# 40_Flash-eMMC_Flash.net
KiCad netlist of a schematic drawn in Altium Designer
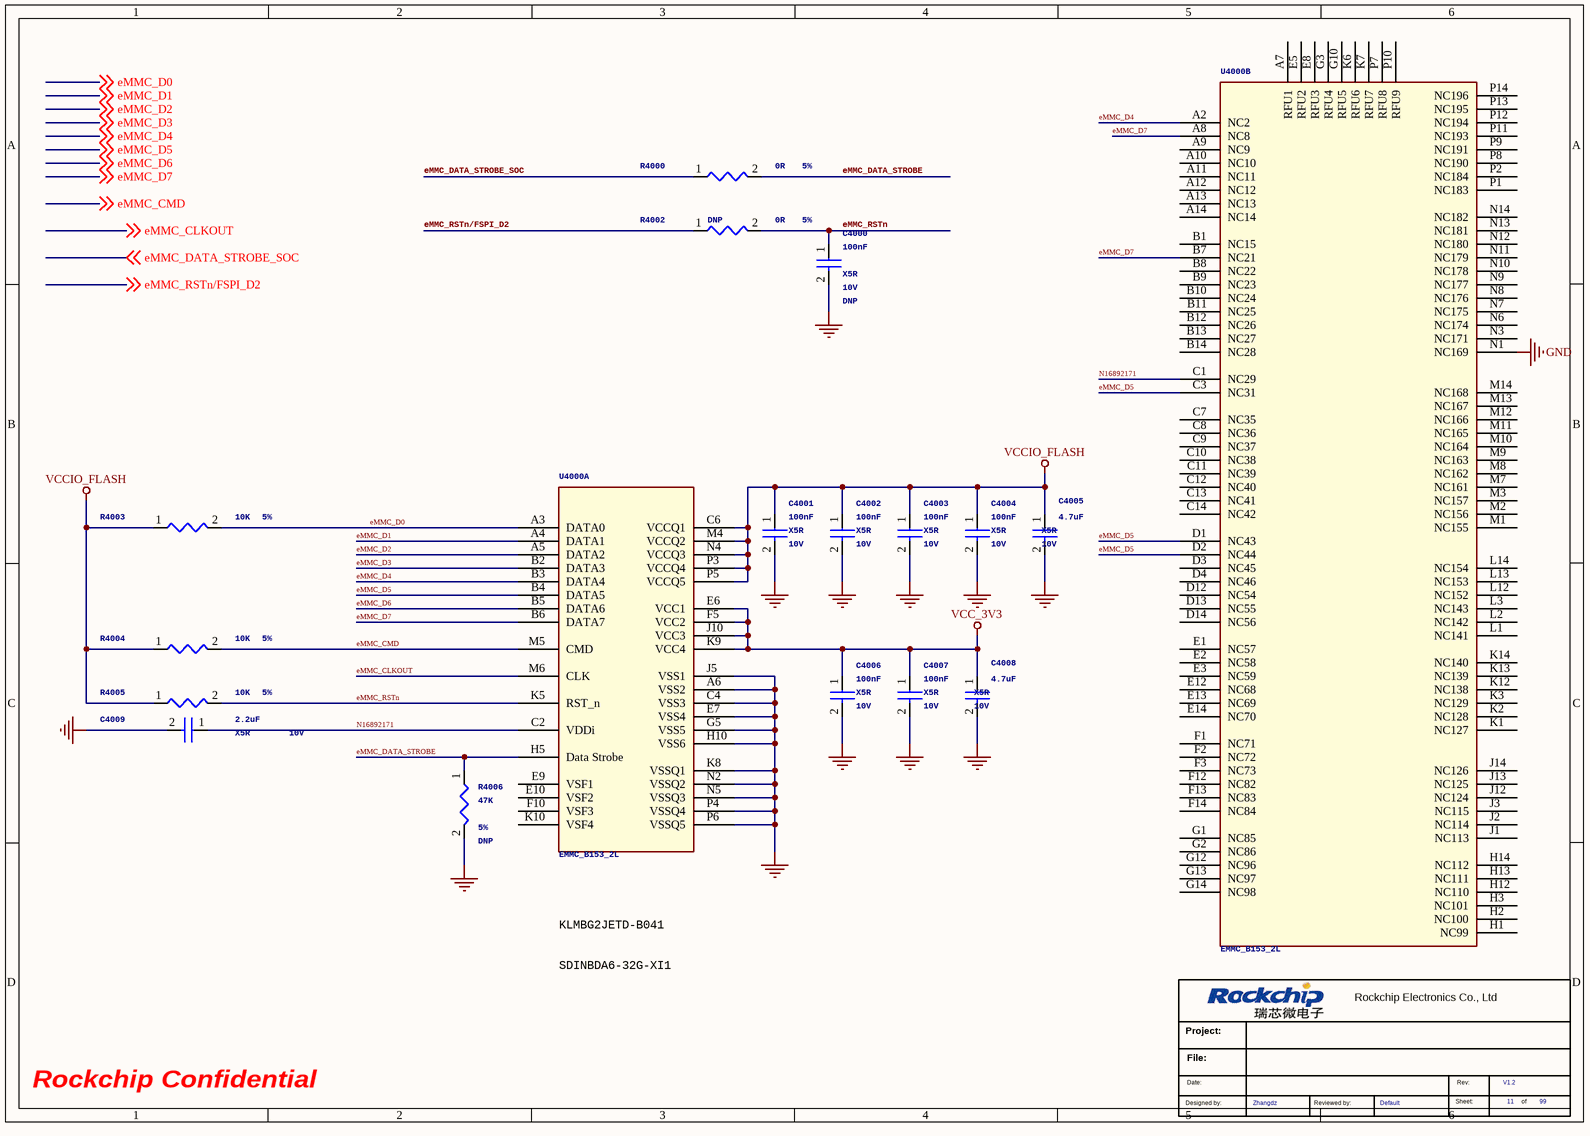
[diagram p0: 40.Flash-eMMC Flash.SchDoc]

(export (version "E")
  (design (tool "Eeschema 10.0.6"))
  (components
    (comp (ref "*")
      (value "Rockchip_new")
      (fields
        (field (name "SCHEMATIC PAGE COUNT") "99")
        (field (name "SCHEMATIC PAGE NUMBER") "11")
        (field (name "DESIGNER") "Zhangdz")
        (field (name "REVISION") "V1.2")
        (field (name "CHECK") "Default")
      )
      (libsource (lib "*") (part "Rockchip_new"))
    )
    (comp (ref "C4000")
      (value "100nF")
      (footprint "C0402")
      (description "cap,100.00nF,+/-10%,10V,X5R,C0402")
      (fields
        (field (name "VOLTAGE") "10V")
        (field (name "DIELECTRIC") "X5R")
        (field (name "OPTION") "DNP")
        (field (name "TOLERANCE") "10%")
        (field (name "MANUFACTURER") "TDK")
        (field (name "CREATED BY") "JJJ")
      )
      (libsource (lib "*") (part "CAP NP"))
    )
    (comp (ref "C4001")
      (value "100nF")
      (footprint "C0402")
      (description "cap,100.00nF,+/-10%,10V,X5R,C0402")
      (fields
        (field (name "VOLTAGE") "10V")
        (field (name "DIELECTRIC") "X5R")
        (field (name "MANUFACTURER") "TDK")
        (field (name "TOLERANCE") "10%")
        (field (name "CREATED BY") "JJJ")
      )
      (libsource (lib "*") (part "CAP NP"))
    )
    (comp (ref "C4002")
      (value "100nF")
      (footprint "C0402")
      (description "cap,100.00nF,+/-10%,10V,X5R,C0402")
      (fields
        (field (name "VOLTAGE") "10V")
        (field (name "DIELECTRIC") "X5R")
        (field (name "TOLERANCE") "10%")
        (field (name "MANUFACTURER") "TDK")
        (field (name "CREATED BY") "JJJ")
      )
      (libsource (lib "*") (part "CAP NP"))
    )
    (comp (ref "C4003")
      (value "100nF")
      (footprint "C0402")
      (description "cap,100.00nF,+/-10%,10V,X5R,C0402")
      (fields
        (field (name "VOLTAGE") "10V")
        (field (name "DIELECTRIC") "X5R")
        (field (name "TOLERANCE") "10%")
        (field (name "MANUFACTURER") "TDK")
        (field (name "CREATED BY") "JJJ")
      )
      (libsource (lib "*") (part "CAP NP"))
    )
    (comp (ref "C4004")
      (value "100nF")
      (footprint "C0402")
      (description "cap,100.00nF,+/-10%,10V,X5R,C0402")
      (fields
        (field (name "VOLTAGE") "10V")
        (field (name "DIELECTRIC") "X5R")
        (field (name "MANUFACTURER") "TDK")
        (field (name "TOLERANCE") "10%")
        (field (name "CREATED BY") "JJJ")
      )
      (libsource (lib "*") (part "CAP NP"))
    )
    (comp (ref "C4005")
      (value "4.7uF")
      (footprint "C0603")
      (description "cap,4.70uF,+/-10%,10V,X5R,C0603")
      (fields
        (field (name "VOLTAGE") "10V")
        (field (name "DIELECTRIC") "X5R")
        (field (name "MANUFACTURER") "TDK")
        (field (name "TOLERANCE") "10%")
        (field (name "CREATED BY") "JJJ")
      )
      (libsource (lib "*") (part "CAP NP"))
    )
    (comp (ref "C4006")
      (value "100nF")
      (footprint "C0402")
      (description "cap,100.00nF,+/-10%,10V,X5R,C0402")
      (fields
        (field (name "VOLTAGE") "10V")
        (field (name "DIELECTRIC") "X5R")
        (field (name "TOLERANCE") "10%")
        (field (name "MANUFACTURER") "TDK")
        (field (name "CREATED BY") "JJJ")
      )
      (libsource (lib "*") (part "CAP NP"))
    )
    (comp (ref "C4007")
      (value "100nF")
      (footprint "C0402")
      (description "cap,100.00nF,+/-10%,10V,X5R,C0402")
      (fields
        (field (name "VOLTAGE") "10V")
        (field (name "DIELECTRIC") "X5R")
        (field (name "TOLERANCE") "10%")
        (field (name "MANUFACTURER") "TDK")
        (field (name "CREATED BY") "JJJ")
      )
      (libsource (lib "*") (part "CAP NP"))
    )
    (comp (ref "C4008")
      (value "4.7uF")
      (footprint "C0603")
      (description "cap,4.70uF,+/-10%,10V,X5R,C0603")
      (fields
        (field (name "VOLTAGE") "10V")
        (field (name "DIELECTRIC") "X5R")
        (field (name "MANUFACTURER") "TDK")
        (field (name "TOLERANCE") "10%")
        (field (name "CREATED BY") "JJJ")
      )
      (libsource (lib "*") (part "CAP NP"))
    )
    (comp (ref "C4009")
      (value "2.2uF")
      (footprint "C0402")
      (description "cap,2.20uF,+/-10%,10V,X5R,C0402")
      (fields
        (field (name "VOLTAGE") "10V")
        (field (name "DIELECTRIC") "X5R")
        (field (name "TOLERANCE") "10%")
        (field (name "MANUFACTURER") "TDK")
        (field (name "CREATED BY") "JJJ")
      )
      (libsource (lib "*") (part "CAP NP"))
    )
    (comp (ref "R4000")
      (value "0R")
      (footprint "R0402")
      (description "通用厚膜电阻,0R,+/-5%,R0402,1/16W.")
      (fields
        (field (name "TOLERANCE") "5%")
        (field (name "MANUFACTURER") "YAGEO")
        (field (name "CREATED BY") "YTL")
      )
      (libsource (lib "*") (part "RESISTOR"))
    )
    (comp (ref "R4002")
      (value "0R")
      (footprint "R0402")
      (description "通用厚膜电阻,0R,+/-5%,R0402,1/16W.")
      (fields
        (field (name "TOLERANCE") "5%")
        (field (name "MANUFACTURER") "YAGEO")
        (field (name "OPTION") "DNP")
        (field (name "CREATED BY") "YTL")
      )
      (libsource (lib "*") (part "RESISTOR"))
    )
    (comp (ref "R4003")
      (value "10K")
      (footprint "R0402")
      (description "通用厚膜电阻,10K,+/-5%,R0402,1/16W.")
      (fields
        (field (name "TOLERANCE") "5%")
        (field (name "MANUFACTURER") "YAGEO")
        (field (name "CREATED BY") "YTL")
      )
      (libsource (lib "*") (part "RESISTOR"))
    )
    (comp (ref "R4004")
      (value "10K")
      (footprint "R0402")
      (description "通用厚膜电阻,10K,+/-5%,R0402,1/16W.")
      (fields
        (field (name "TOLERANCE") "5%")
        (field (name "MANUFACTURER") "YAGEO")
        (field (name "CREATED BY") "YTL")
      )
      (libsource (lib "*") (part "RESISTOR"))
    )
    (comp (ref "R4005")
      (value "10K")
      (footprint "R0402")
      (description "通用厚膜电阻,10K,+/-5%,R0402,1/16W.")
      (fields
        (field (name "TOLERANCE") "5%")
        (field (name "MANUFACTURER") "YAGEO")
        (field (name "CREATED BY") "YTL")
      )
      (libsource (lib "*") (part "RESISTOR"))
    )
    (comp (ref "R4006")
      (value "47K")
      (footprint "R0402")
      (description "通用厚膜电阻,47K,+/-5%,R0402,1/16W.")
      (fields
        (field (name "TOLERANCE") "5%")
        (field (name "OPTION") "DNP")
        (field (name "MANUFACTURER") "YAGEO")
        (field (name "CREATED BY") "YTL")
      )
      (libsource (lib "*") (part "RESISTOR"))
    )
    (comp (ref "U4000")
      (value "EMMC_B153_2L")
      (footprint "BGA153_13RX11R5X0R9_2L")
      (description "EMMC_B153_2L,更好的满足工艺需求，Fanout方式部分走线跨接再球位上，挖除A1\\C5球位")
      (fields (field (name "CREATED BY") "YWQ"))
      (libsource (lib "*") (part "INAND_EMMC_153_2L"))
    )
  )
  (nets
    (net (code "1") (name "/N16892171") (class "Default")
      (node (ref "C4009") (pin "1") (pinfunction "1_1") (pintype "passive"))
      (node (ref "U4000") (pin "C1") (pinfunction "NC29_C1") (pintype "passive"))
      (node (ref "U4000") (pin "C2") (pinfunction "VDDi_C2") (pintype "passive"))
    )
    (net (code "2") (name "/eMMC_DATA_STROBE") (class "Default")
      (node (ref "R4000") (pin "2") (pinfunction "2_2") (pintype "passive"))
      (node (ref "R4006") (pin "1") (pinfunction "1_1") (pintype "passive"))
      (node (ref "U4000") (pin "H5") (pinfunction "Data_Strobe_H5") (pintype "passive"))
    )
    (net (code "3") (name "/eMMC_RSTn") (class "Default")
      (node (ref "C4000") (pin "1") (pinfunction "1_1") (pintype "passive"))
      (node (ref "R4002") (pin "2") (pinfunction "2_2") (pintype "passive"))
      (node (ref "R4005") (pin "2") (pinfunction "2_2") (pintype "passive"))
      (node (ref "U4000") (pin "K5") (pinfunction "RST_n_K5") (pintype "passive"))
    )
    (net (code "4") (name "GND") (class "Default")
      (node (ref "C4000") (pin "2") (pinfunction "2_2") (pintype "passive"))
      (node (ref "C4001") (pin "2") (pinfunction "2_2") (pintype "passive"))
      (node (ref "C4002") (pin "2") (pinfunction "2_2") (pintype "passive"))
      (node (ref "C4003") (pin "2") (pinfunction "2_2") (pintype "passive"))
      (node (ref "C4004") (pin "2") (pinfunction "2_2") (pintype "passive"))
      (node (ref "C4005") (pin "2") (pinfunction "2_2") (pintype "passive"))
      (node (ref "C4006") (pin "2") (pinfunction "2_2") (pintype "passive"))
      (node (ref "C4007") (pin "2") (pinfunction "2_2") (pintype "passive"))
      (node (ref "C4008") (pin "2") (pinfunction "2_2") (pintype "passive"))
      (node (ref "C4009") (pin "2") (pinfunction "2_2") (pintype "passive"))
      (node (ref "R4006") (pin "2") (pinfunction "2_2") (pintype "passive"))
      (node (ref "U4000") (pin "A6") (pinfunction "VSS2_A6") (pintype "passive"))
      (node (ref "U4000") (pin "C4") (pinfunction "VSS3_C4") (pintype "passive"))
      (node (ref "U4000") (pin "E7") (pinfunction "VSS4_E7") (pintype "passive"))
      (node (ref "U4000") (pin "G5") (pinfunction "VSS5_G5") (pintype "passive"))
      (node (ref "U4000") (pin "H10") (pinfunction "VSS6_H10") (pintype "passive"))
      (node (ref "U4000") (pin "J5") (pinfunction "VSS1_J5") (pintype "passive"))
      (node (ref "U4000") (pin "K8") (pinfunction "VSSQ1_K8") (pintype "passive"))
      (node (ref "U4000") (pin "N1") (pinfunction "NC169_N1") (pintype "passive"))
      (node (ref "U4000") (pin "N2") (pinfunction "VSSQ2_N2") (pintype "passive"))
      (node (ref "U4000") (pin "N5") (pinfunction "VSSQ3_N5") (pintype "passive"))
      (node (ref "U4000") (pin "P4") (pinfunction "VSSQ4_P4") (pintype "passive"))
      (node (ref "U4000") (pin "P6") (pinfunction "VSSQ5_P6") (pintype "passive"))
    )
    (net (code "5") (name "VCCIO_FLASH") (class "Default")
      (node (ref "C4001") (pin "1") (pinfunction "1_1") (pintype "passive"))
      (node (ref "C4002") (pin "1") (pinfunction "1_1") (pintype "passive"))
      (node (ref "C4003") (pin "1") (pinfunction "1_1") (pintype "passive"))
      (node (ref "C4004") (pin "1") (pinfunction "1_1") (pintype "passive"))
      (node (ref "C4005") (pin "1") (pinfunction "1_1") (pintype "passive"))
      (node (ref "R4003") (pin "1") (pinfunction "1_1") (pintype "passive"))
      (node (ref "R4004") (pin "1") (pinfunction "1_1") (pintype "passive"))
      (node (ref "R4005") (pin "1") (pinfunction "1_1") (pintype "passive"))
      (node (ref "U4000") (pin "C6") (pinfunction "VCCQ1_C6") (pintype "passive"))
      (node (ref "U4000") (pin "M4") (pinfunction "VCCQ2_M4") (pintype "passive"))
      (node (ref "U4000") (pin "N4") (pinfunction "VCCQ3_N4") (pintype "passive"))
      (node (ref "U4000") (pin "P3") (pinfunction "VCCQ4_P3") (pintype "passive"))
      (node (ref "U4000") (pin "P5") (pinfunction "VCCQ5_P5") (pintype "passive"))
    )
    (net (code "6") (name "VCC_3V3") (class "Default")
      (node (ref "C4006") (pin "1") (pinfunction "1_1") (pintype "passive"))
      (node (ref "C4007") (pin "1") (pinfunction "1_1") (pintype "passive"))
      (node (ref "C4008") (pin "1") (pinfunction "1_1") (pintype "passive"))
      (node (ref "U4000") (pin "E6") (pinfunction "VCC1_E6") (pintype "passive"))
      (node (ref "U4000") (pin "F5") (pinfunction "VCC2_F5") (pintype "passive"))
      (node (ref "U4000") (pin "J10") (pinfunction "VCC3_J10") (pintype "passive"))
      (node (ref "U4000") (pin "K9") (pinfunction "VCC4_K9") (pintype "passive"))
    )
    (net (code "7") (name "eMMC_CLKOUT") (class "Default")
      (node (ref "U4000") (pin "M6") (pinfunction "CLK_M6") (pintype "passive"))
    )
    (net (code "8") (name "eMMC_CMD") (class "Default")
      (node (ref "R4004") (pin "2") (pinfunction "2_2") (pintype "passive"))
      (node (ref "U4000") (pin "M5") (pinfunction "CMD_M5") (pintype "passive"))
    )
    (net (code "9") (name "eMMC_D0") (class "Default")
      (node (ref "R4003") (pin "2") (pinfunction "2_2") (pintype "passive"))
      (node (ref "U4000") (pin "A3") (pinfunction "DATA0_A3") (pintype "passive"))
    )
    (net (code "10") (name "eMMC_D1") (class "Default")
      (node (ref "U4000") (pin "A4") (pinfunction "DATA1_A4") (pintype "passive"))
    )
    (net (code "11") (name "eMMC_D2") (class "Default")
      (node (ref "U4000") (pin "A5") (pinfunction "DATA2_A5") (pintype "passive"))
    )
    (net (code "12") (name "eMMC_D3") (class "Default")
      (node (ref "U4000") (pin "B2") (pinfunction "DATA3_B2") (pintype "passive"))
    )
    (net (code "13") (name "eMMC_D4") (class "Default")
      (node (ref "U4000") (pin "A2") (pinfunction "NC2_A2") (pintype "passive"))
      (node (ref "U4000") (pin "B3") (pinfunction "DATA4_B3") (pintype "passive"))
    )
    (net (code "14") (name "eMMC_D5") (class "Default")
      (node (ref "U4000") (pin "B4") (pinfunction "DATA5_B4") (pintype "passive"))
      (node (ref "U4000") (pin "C3") (pinfunction "NC31_C3") (pintype "passive"))
      (node (ref "U4000") (pin "D1") (pinfunction "NC43_D1") (pintype "passive"))
      (node (ref "U4000") (pin "D2") (pinfunction "NC44_D2") (pintype "passive"))
    )
    (net (code "15") (name "eMMC_D6") (class "Default")
      (node (ref "U4000") (pin "B5") (pinfunction "DATA6_B5") (pintype "passive"))
    )
    (net (code "16") (name "eMMC_D7") (class "Default")
      (node (ref "U4000") (pin "A8") (pinfunction "NC8_A8") (pintype "passive"))
      (node (ref "U4000") (pin "B6") (pinfunction "DATA7_B6") (pintype "passive"))
      (node (ref "U4000") (pin "B7") (pinfunction "NC21_B7") (pintype "passive"))
    )
    (net (code "17") (name "eMMC_DATA_STROBE_SOC") (class "Default")
      (node (ref "R4000") (pin "1") (pinfunction "1_1") (pintype "passive"))
    )
    (net (code "18") (name "eMMC_RSTn{slash}FSPI_D2") (class "Default")
      (node (ref "R4002") (pin "1") (pinfunction "1_1") (pintype "passive"))
    )
    (net (code "19") (name "unconnected-(U4000A-VSF1-PadE9)") (class "Default")
      (node (ref "U4000") (pin "E9") (pinfunction "VSF1_E9") (pintype "passive"))
    )
    (net (code "20") (name "unconnected-(U4000A-VSF2-PadE10)") (class "Default")
      (node (ref "U4000") (pin "E10") (pinfunction "VSF2_E10") (pintype "passive"))
    )
    (net (code "21") (name "unconnected-(U4000A-VSF3-PadF10)") (class "Default")
      (node (ref "U4000") (pin "F10") (pinfunction "VSF3_F10") (pintype "passive"))
    )
    (net (code "22") (name "unconnected-(U4000A-VSF4-PadK10)") (class "Default")
      (node (ref "U4000") (pin "K10") (pinfunction "VSF4_K10") (pintype "passive"))
    )
    (net (code "23") (name "unconnected-(U4000B-NC9-PadA9)") (class "Default")
      (node (ref "U4000") (pin "A9") (pinfunction "NC9_A9") (pintype "passive"))
    )
    (net (code "24") (name "unconnected-(U4000B-NC10-PadA10)") (class "Default")
      (node (ref "U4000") (pin "A10") (pinfunction "NC10_A10") (pintype "passive"))
    )
    (net (code "25") (name "unconnected-(U4000B-NC11-PadA11)") (class "Default")
      (node (ref "U4000") (pin "A11") (pinfunction "NC11_A11") (pintype "passive"))
    )
    (net (code "26") (name "unconnected-(U4000B-NC12-PadA12)") (class "Default")
      (node (ref "U4000") (pin "A12") (pinfunction "NC12_A12") (pintype "passive"))
    )
    (net (code "27") (name "unconnected-(U4000B-NC13-PadA13)") (class "Default")
      (node (ref "U4000") (pin "A13") (pinfunction "NC13_A13") (pintype "passive"))
    )
    (net (code "28") (name "unconnected-(U4000B-NC14-PadA14)") (class "Default")
      (node (ref "U4000") (pin "A14") (pinfunction "NC14_A14") (pintype "passive"))
    )
    (net (code "29") (name "unconnected-(U4000B-NC15-PadB1)") (class "Default")
      (node (ref "U4000") (pin "B1") (pinfunction "NC15_B1") (pintype "passive"))
    )
    (net (code "30") (name "unconnected-(U4000B-NC22-PadB8)") (class "Default")
      (node (ref "U4000") (pin "B8") (pinfunction "NC22_B8") (pintype "passive"))
    )
    (net (code "31") (name "unconnected-(U4000B-NC23-PadB9)") (class "Default")
      (node (ref "U4000") (pin "B9") (pinfunction "NC23_B9") (pintype "passive"))
    )
    (net (code "32") (name "unconnected-(U4000B-NC24-PadB10)") (class "Default")
      (node (ref "U4000") (pin "B10") (pinfunction "NC24_B10") (pintype "passive"))
    )
    (net (code "33") (name "unconnected-(U4000B-NC25-PadB11)") (class "Default")
      (node (ref "U4000") (pin "B11") (pinfunction "NC25_B11") (pintype "passive"))
    )
    (net (code "34") (name "unconnected-(U4000B-NC26-PadB12)") (class "Default")
      (node (ref "U4000") (pin "B12") (pinfunction "NC26_B12") (pintype "passive"))
    )
    (net (code "35") (name "unconnected-(U4000B-NC27-PadB13)") (class "Default")
      (node (ref "U4000") (pin "B13") (pinfunction "NC27_B13") (pintype "passive"))
    )
    (net (code "36") (name "unconnected-(U4000B-NC28-PadB14)") (class "Default")
      (node (ref "U4000") (pin "B14") (pinfunction "NC28_B14") (pintype "passive"))
    )
    (net (code "37") (name "unconnected-(U4000B-NC35-PadC7)") (class "Default")
      (node (ref "U4000") (pin "C7") (pinfunction "NC35_C7") (pintype "passive"))
    )
    (net (code "38") (name "unconnected-(U4000B-NC36-PadC8)") (class "Default")
      (node (ref "U4000") (pin "C8") (pinfunction "NC36_C8") (pintype "passive"))
    )
    (net (code "39") (name "unconnected-(U4000B-NC37-PadC9)") (class "Default")
      (node (ref "U4000") (pin "C9") (pinfunction "NC37_C9") (pintype "passive"))
    )
    (net (code "40") (name "unconnected-(U4000B-NC38-PadC10)") (class "Default")
      (node (ref "U4000") (pin "C10") (pinfunction "NC38_C10") (pintype "passive"))
    )
    (net (code "41") (name "unconnected-(U4000B-NC39-PadC11)") (class "Default")
      (node (ref "U4000") (pin "C11") (pinfunction "NC39_C11") (pintype "passive"))
    )
    (net (code "42") (name "unconnected-(U4000B-NC40-PadC12)") (class "Default")
      (node (ref "U4000") (pin "C12") (pinfunction "NC40_C12") (pintype "passive"))
    )
    (net (code "43") (name "unconnected-(U4000B-NC41-PadC13)") (class "Default")
      (node (ref "U4000") (pin "C13") (pinfunction "NC41_C13") (pintype "passive"))
    )
    (net (code "44") (name "unconnected-(U4000B-NC42-PadC14)") (class "Default")
      (node (ref "U4000") (pin "C14") (pinfunction "NC42_C14") (pintype "passive"))
    )
    (net (code "45") (name "unconnected-(U4000B-NC45-PadD3)") (class "Default")
      (node (ref "U4000") (pin "D3") (pinfunction "NC45_D3") (pintype "passive"))
    )
    (net (code "46") (name "unconnected-(U4000B-NC46-PadD4)") (class "Default")
      (node (ref "U4000") (pin "D4") (pinfunction "NC46_D4") (pintype "passive"))
    )
    (net (code "47") (name "unconnected-(U4000B-NC54-PadD12)") (class "Default")
      (node (ref "U4000") (pin "D12") (pinfunction "NC54_D12") (pintype "passive"))
    )
    (net (code "48") (name "unconnected-(U4000B-NC55-PadD13)") (class "Default")
      (node (ref "U4000") (pin "D13") (pinfunction "NC55_D13") (pintype "passive"))
    )
    (net (code "49") (name "unconnected-(U4000B-NC56-PadD14)") (class "Default")
      (node (ref "U4000") (pin "D14") (pinfunction "NC56_D14") (pintype "passive"))
    )
    (net (code "50") (name "unconnected-(U4000B-NC57-PadE1)") (class "Default")
      (node (ref "U4000") (pin "E1") (pinfunction "NC57_E1") (pintype "passive"))
    )
    (net (code "51") (name "unconnected-(U4000B-NC58-PadE2)") (class "Default")
      (node (ref "U4000") (pin "E2") (pinfunction "NC58_E2") (pintype "passive"))
    )
    (net (code "52") (name "unconnected-(U4000B-NC59-PadE3)") (class "Default")
      (node (ref "U4000") (pin "E3") (pinfunction "NC59_E3") (pintype "passive"))
    )
    (net (code "53") (name "unconnected-(U4000B-NC68-PadE12)") (class "Default")
      (node (ref "U4000") (pin "E12") (pinfunction "NC68_E12") (pintype "passive"))
    )
    (net (code "54") (name "unconnected-(U4000B-NC69-PadE13)") (class "Default")
      (node (ref "U4000") (pin "E13") (pinfunction "NC69_E13") (pintype "passive"))
    )
    (net (code "55") (name "unconnected-(U4000B-NC70-PadE14)") (class "Default")
      (node (ref "U4000") (pin "E14") (pinfunction "NC70_E14") (pintype "passive"))
    )
    (net (code "56") (name "unconnected-(U4000B-NC71-PadF1)") (class "Default")
      (node (ref "U4000") (pin "F1") (pinfunction "NC71_F1") (pintype "passive"))
    )
    (net (code "57") (name "unconnected-(U4000B-NC72-PadF2)") (class "Default")
      (node (ref "U4000") (pin "F2") (pinfunction "NC72_F2") (pintype "passive"))
    )
    (net (code "58") (name "unconnected-(U4000B-NC73-PadF3)") (class "Default")
      (node (ref "U4000") (pin "F3") (pinfunction "NC73_F3") (pintype "passive"))
    )
    (net (code "59") (name "unconnected-(U4000B-NC82-PadF12)") (class "Default")
      (node (ref "U4000") (pin "F12") (pinfunction "NC82_F12") (pintype "passive"))
    )
    (net (code "60") (name "unconnected-(U4000B-NC83-PadF13)") (class "Default")
      (node (ref "U4000") (pin "F13") (pinfunction "NC83_F13") (pintype "passive"))
    )
    (net (code "61") (name "unconnected-(U4000B-NC84-PadF14)") (class "Default")
      (node (ref "U4000") (pin "F14") (pinfunction "NC84_F14") (pintype "passive"))
    )
    (net (code "62") (name "unconnected-(U4000B-NC85-PadG1)") (class "Default")
      (node (ref "U4000") (pin "G1") (pinfunction "NC85_G1") (pintype "passive"))
    )
    (net (code "63") (name "unconnected-(U4000B-NC86-PadG2)") (class "Default")
      (node (ref "U4000") (pin "G2") (pinfunction "NC86_G2") (pintype "passive"))
    )
    (net (code "64") (name "unconnected-(U4000B-NC96-PadG12)") (class "Default")
      (node (ref "U4000") (pin "G12") (pinfunction "NC96_G12") (pintype "passive"))
    )
    (net (code "65") (name "unconnected-(U4000B-NC97-PadG13)") (class "Default")
      (node (ref "U4000") (pin "G13") (pinfunction "NC97_G13") (pintype "passive"))
    )
    (net (code "66") (name "unconnected-(U4000B-NC98-PadG14)") (class "Default")
      (node (ref "U4000") (pin "G14") (pinfunction "NC98_G14") (pintype "passive"))
    )
    (net (code "67") (name "unconnected-(U4000B-NC99-PadH1)") (class "Default")
      (node (ref "U4000") (pin "H1") (pinfunction "NC99_H1") (pintype "passive"))
    )
    (net (code "68") (name "unconnected-(U4000B-NC100-PadH2)") (class "Default")
      (node (ref "U4000") (pin "H2") (pinfunction "NC100_H2") (pintype "passive"))
    )
    (net (code "69") (name "unconnected-(U4000B-NC101-PadH3)") (class "Default")
      (node (ref "U4000") (pin "H3") (pinfunction "NC101_H3") (pintype "passive"))
    )
    (net (code "70") (name "unconnected-(U4000B-NC110-PadH12)") (class "Default")
      (node (ref "U4000") (pin "H12") (pinfunction "NC110_H12") (pintype "passive"))
    )
    (net (code "71") (name "unconnected-(U4000B-NC111-PadH13)") (class "Default")
      (node (ref "U4000") (pin "H13") (pinfunction "NC111_H13") (pintype "passive"))
    )
    (net (code "72") (name "unconnected-(U4000B-NC112-PadH14)") (class "Default")
      (node (ref "U4000") (pin "H14") (pinfunction "NC112_H14") (pintype "passive"))
    )
    (net (code "73") (name "unconnected-(U4000B-NC113-PadJ1)") (class "Default")
      (node (ref "U4000") (pin "J1") (pinfunction "NC113_J1") (pintype "passive"))
    )
    (net (code "74") (name "unconnected-(U4000B-NC114-PadJ2)") (class "Default")
      (node (ref "U4000") (pin "J2") (pinfunction "NC114_J2") (pintype "passive"))
    )
    (net (code "75") (name "unconnected-(U4000B-NC115-PadJ3)") (class "Default")
      (node (ref "U4000") (pin "J3") (pinfunction "NC115_J3") (pintype "passive"))
    )
    (net (code "76") (name "unconnected-(U4000B-NC124-PadJ12)") (class "Default")
      (node (ref "U4000") (pin "J12") (pinfunction "NC124_J12") (pintype "passive"))
    )
    (net (code "77") (name "unconnected-(U4000B-NC125-PadJ13)") (class "Default")
      (node (ref "U4000") (pin "J13") (pinfunction "NC125_J13") (pintype "passive"))
    )
    (net (code "78") (name "unconnected-(U4000B-NC126-PadJ14)") (class "Default")
      (node (ref "U4000") (pin "J14") (pinfunction "NC126_J14") (pintype "passive"))
    )
    (net (code "79") (name "unconnected-(U4000B-NC127-PadK1)") (class "Default")
      (node (ref "U4000") (pin "K1") (pinfunction "NC127_K1") (pintype "passive"))
    )
    (net (code "80") (name "unconnected-(U4000B-NC128-PadK2)") (class "Default")
      (node (ref "U4000") (pin "K2") (pinfunction "NC128_K2") (pintype "passive"))
    )
    (net (code "81") (name "unconnected-(U4000B-NC129-PadK3)") (class "Default")
      (node (ref "U4000") (pin "K3") (pinfunction "NC129_K3") (pintype "passive"))
    )
    (net (code "82") (name "unconnected-(U4000B-NC138-PadK12)") (class "Default")
      (node (ref "U4000") (pin "K12") (pinfunction "NC138_K12") (pintype "passive"))
    )
    (net (code "83") (name "unconnected-(U4000B-NC139-PadK13)") (class "Default")
      (node (ref "U4000") (pin "K13") (pinfunction "NC139_K13") (pintype "passive"))
    )
    (net (code "84") (name "unconnected-(U4000B-NC140-PadK14)") (class "Default")
      (node (ref "U4000") (pin "K14") (pinfunction "NC140_K14") (pintype "passive"))
    )
    (net (code "85") (name "unconnected-(U4000B-NC141-PadL1)") (class "Default")
      (node (ref "U4000") (pin "L1") (pinfunction "NC141_L1") (pintype "passive"))
    )
    (net (code "86") (name "unconnected-(U4000B-NC142-PadL2)") (class "Default")
      (node (ref "U4000") (pin "L2") (pinfunction "NC142_L2") (pintype "passive"))
    )
    (net (code "87") (name "unconnected-(U4000B-NC143-PadL3)") (class "Default")
      (node (ref "U4000") (pin "L3") (pinfunction "NC143_L3") (pintype "passive"))
    )
    (net (code "88") (name "unconnected-(U4000B-NC152-PadL12)") (class "Default")
      (node (ref "U4000") (pin "L12") (pinfunction "NC152_L12") (pintype "passive"))
    )
    (net (code "89") (name "unconnected-(U4000B-NC153-PadL13)") (class "Default")
      (node (ref "U4000") (pin "L13") (pinfunction "NC153_L13") (pintype "passive"))
    )
    (net (code "90") (name "unconnected-(U4000B-NC154-PadL14)") (class "Default")
      (node (ref "U4000") (pin "L14") (pinfunction "NC154_L14") (pintype "passive"))
    )
    (net (code "91") (name "unconnected-(U4000B-NC155-PadM1)") (class "Default")
      (node (ref "U4000") (pin "M1") (pinfunction "NC155_M1") (pintype "passive"))
    )
    (net (code "92") (name "unconnected-(U4000B-NC156-PadM2)") (class "Default")
      (node (ref "U4000") (pin "M2") (pinfunction "NC156_M2") (pintype "passive"))
    )
    (net (code "93") (name "unconnected-(U4000B-NC157-PadM3)") (class "Default")
      (node (ref "U4000") (pin "M3") (pinfunction "NC157_M3") (pintype "passive"))
    )
    (net (code "94") (name "unconnected-(U4000B-NC161-PadM7)") (class "Default")
      (node (ref "U4000") (pin "M7") (pinfunction "NC161_M7") (pintype "passive"))
    )
    (net (code "95") (name "unconnected-(U4000B-NC162-PadM8)") (class "Default")
      (node (ref "U4000") (pin "M8") (pinfunction "NC162_M8") (pintype "passive"))
    )
    (net (code "96") (name "unconnected-(U4000B-NC163-PadM9)") (class "Default")
      (node (ref "U4000") (pin "M9") (pinfunction "NC163_M9") (pintype "passive"))
    )
    (net (code "97") (name "unconnected-(U4000B-NC164-PadM10)") (class "Default")
      (node (ref "U4000") (pin "M10") (pinfunction "NC164_M10") (pintype "passive"))
    )
    (net (code "98") (name "unconnected-(U4000B-NC165-PadM11)") (class "Default")
      (node (ref "U4000") (pin "M11") (pinfunction "NC165_M11") (pintype "passive"))
    )
    (net (code "99") (name "unconnected-(U4000B-NC166-PadM12)") (class "Default")
      (node (ref "U4000") (pin "M12") (pinfunction "NC166_M12") (pintype "passive"))
    )
    (net (code "100") (name "unconnected-(U4000B-NC167-PadM13)") (class "Default")
      (node (ref "U4000") (pin "M13") (pinfunction "NC167_M13") (pintype "passive"))
    )
    (net (code "101") (name "unconnected-(U4000B-NC168-PadM14)") (class "Default")
      (node (ref "U4000") (pin "M14") (pinfunction "NC168_M14") (pintype "passive"))
    )
    (net (code "102") (name "unconnected-(U4000B-NC171-PadN3)") (class "Default")
      (node (ref "U4000") (pin "N3") (pinfunction "NC171_N3") (pintype "passive"))
    )
    (net (code "103") (name "unconnected-(U4000B-NC174-PadN6)") (class "Default")
      (node (ref "U4000") (pin "N6") (pinfunction "NC174_N6") (pintype "passive"))
    )
    (net (code "104") (name "unconnected-(U4000B-NC175-PadN7)") (class "Default")
      (node (ref "U4000") (pin "N7") (pinfunction "NC175_N7") (pintype "passive"))
    )
    (net (code "105") (name "unconnected-(U4000B-NC176-PadN8)") (class "Default")
      (node (ref "U4000") (pin "N8") (pinfunction "NC176_N8") (pintype "passive"))
    )
    (net (code "106") (name "unconnected-(U4000B-NC177-PadN9)") (class "Default")
      (node (ref "U4000") (pin "N9") (pinfunction "NC177_N9") (pintype "passive"))
    )
    (net (code "107") (name "unconnected-(U4000B-NC178-PadN10)") (class "Default")
      (node (ref "U4000") (pin "N10") (pinfunction "NC178_N10") (pintype "passive"))
    )
    (net (code "108") (name "unconnected-(U4000B-NC179-PadN11)") (class "Default")
      (node (ref "U4000") (pin "N11") (pinfunction "NC179_N11") (pintype "passive"))
    )
    (net (code "109") (name "unconnected-(U4000B-NC180-PadN12)") (class "Default")
      (node (ref "U4000") (pin "N12") (pinfunction "NC180_N12") (pintype "passive"))
    )
    (net (code "110") (name "unconnected-(U4000B-NC181-PadN13)") (class "Default")
      (node (ref "U4000") (pin "N13") (pinfunction "NC181_N13") (pintype "passive"))
    )
    (net (code "111") (name "unconnected-(U4000B-NC182-PadN14)") (class "Default")
      (node (ref "U4000") (pin "N14") (pinfunction "NC182_N14") (pintype "passive"))
    )
    (net (code "112") (name "unconnected-(U4000B-NC183-PadP1)") (class "Default")
      (node (ref "U4000") (pin "P1") (pinfunction "NC183_P1") (pintype "passive"))
    )
    (net (code "113") (name "unconnected-(U4000B-NC184-PadP2)") (class "Default")
      (node (ref "U4000") (pin "P2") (pinfunction "NC184_P2") (pintype "passive"))
    )
    (net (code "114") (name "unconnected-(U4000B-NC190-PadP8)") (class "Default")
      (node (ref "U4000") (pin "P8") (pinfunction "NC190_P8") (pintype "passive"))
    )
    (net (code "115") (name "unconnected-(U4000B-NC191-PadP9)") (class "Default")
      (node (ref "U4000") (pin "P9") (pinfunction "NC191_P9") (pintype "passive"))
    )
    (net (code "116") (name "unconnected-(U4000B-NC193-PadP11)") (class "Default")
      (node (ref "U4000") (pin "P11") (pinfunction "NC193_P11") (pintype "passive"))
    )
    (net (code "117") (name "unconnected-(U4000B-NC194-PadP12)") (class "Default")
      (node (ref "U4000") (pin "P12") (pinfunction "NC194_P12") (pintype "passive"))
    )
    (net (code "118") (name "unconnected-(U4000B-NC195-PadP13)") (class "Default")
      (node (ref "U4000") (pin "P13") (pinfunction "NC195_P13") (pintype "passive"))
    )
    (net (code "119") (name "unconnected-(U4000B-NC196-PadP14)") (class "Default")
      (node (ref "U4000") (pin "P14") (pinfunction "NC196_P14") (pintype "passive"))
    )
    (net (code "120") (name "unconnected-(U4000B-RFU1-PadA7)") (class "Default")
      (node (ref "U4000") (pin "A7") (pinfunction "RFU1_A7") (pintype "passive"))
    )
    (net (code "121") (name "unconnected-(U4000B-RFU2-PadE5)") (class "Default")
      (node (ref "U4000") (pin "E5") (pinfunction "RFU2_E5") (pintype "passive"))
    )
    (net (code "122") (name "unconnected-(U4000B-RFU3-PadE8)") (class "Default")
      (node (ref "U4000") (pin "E8") (pinfunction "RFU3_E8") (pintype "passive"))
    )
    (net (code "123") (name "unconnected-(U4000B-RFU4-PadG3)") (class "Default")
      (node (ref "U4000") (pin "G3") (pinfunction "RFU4_G3") (pintype "passive"))
    )
    (net (code "124") (name "unconnected-(U4000B-RFU5-PadG10)") (class "Default")
      (node (ref "U4000") (pin "G10") (pinfunction "RFU5_G10") (pintype "passive"))
    )
    (net (code "125") (name "unconnected-(U4000B-RFU6-PadK6)") (class "Default")
      (node (ref "U4000") (pin "K6") (pinfunction "RFU6_K6") (pintype "passive"))
    )
    (net (code "126") (name "unconnected-(U4000B-RFU7-PadK7)") (class "Default")
      (node (ref "U4000") (pin "K7") (pinfunction "RFU7_K7") (pintype "passive"))
    )
    (net (code "127") (name "unconnected-(U4000B-RFU8-PadP7)") (class "Default")
      (node (ref "U4000") (pin "P7") (pinfunction "RFU8_P7") (pintype "passive"))
    )
    (net (code "128") (name "unconnected-(U4000B-RFU9-PadP10)") (class "Default")
      (node (ref "U4000") (pin "P10") (pinfunction "RFU9_P10") (pintype "passive"))
    )
  )
)
